# Connectors.net
KiCad netlist of a schematic drawn in Altium Designer
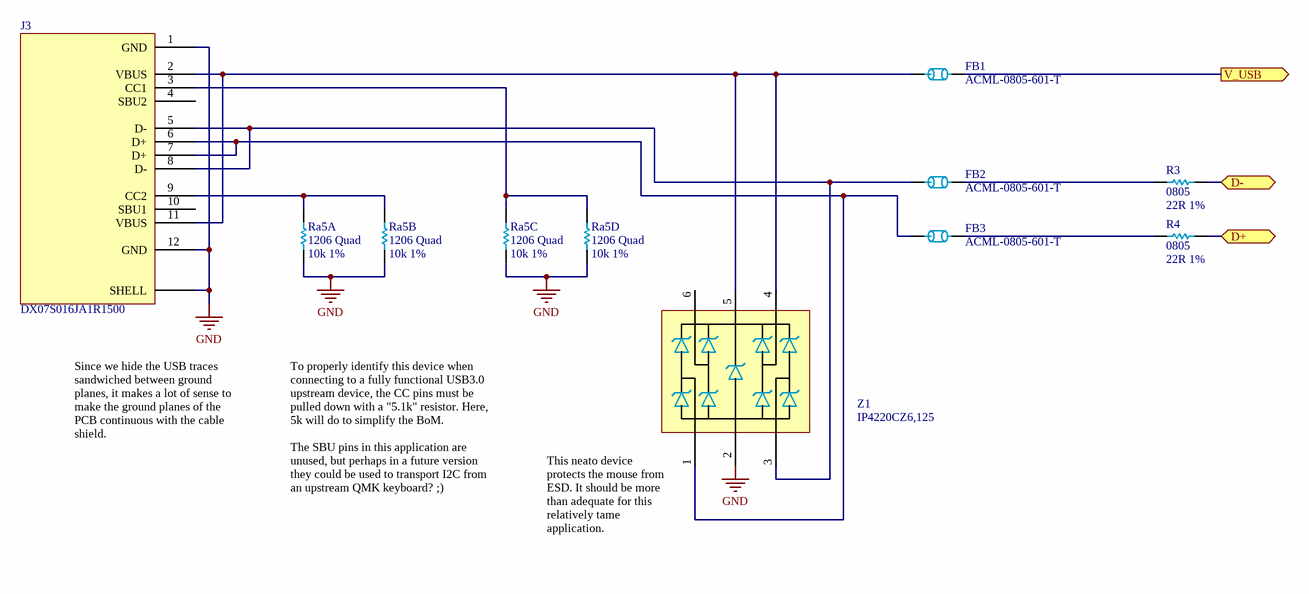
[diagram p0: Connectors.SchDoc]

(export (version "E")
  (design (tool "Eeschema 10.0.6"))
  (components
    (comp (ref "FB1")
      (value "ACML-0805-601-T")
      (footprint "0805")
      (description "FERRITE BEAD 600 OHM 0805 1LN")
      (libsource (lib "Chip_Passives") (part "ACML-0805-601-T"))
    )
    (comp (ref "FB2")
      (value "ACML-0805-601-T")
      (footprint "0805")
      (description "FERRITE BEAD 600 OHM 0805 1LN")
      (libsource (lib "Chip_Passives") (part "ACML-0805-601-T"))
    )
    (comp (ref "FB3")
      (value "ACML-0805-601-T")
      (footprint "0805")
      (description "FERRITE BEAD 600 OHM 0805 1LN")
      (libsource (lib "Chip_Passives") (part "ACML-0805-601-T"))
    )
    (comp (ref "J3")
      (value "DX07S016JA1R1500")
      (footprint "DX07S016JA1R1500")
      (libsource (lib "Connectors") (part "DX07S016JA1R1500"))
    )
    (comp (ref "R3")
      (value "0805")
      (footprint "0805")
      (description "Chip resistor")
      (fields (field (name "ALTIUM_VALUE") "22R 1%"))
      (libsource (lib "Chip_Passives") (part "Res 22R 1% 0805"))
    )
    (comp (ref "R4")
      (value "0805")
      (footprint "0805")
      (description "Chip resistor")
      (fields (field (name "ALTIUM_VALUE") "22R 1%"))
      (libsource (lib "Chip_Passives") (part "Res 22R 1% 0805"))
    )
    (comp (ref "Ra5")
      (value "1206 Quad")
      (footprint "4x 10k 1% - CAC-80P320X160-8M")
      (description "Chip resistor")
      (fields (field (name "ALTIUM_VALUE") "10k 1%"))
      (libsource (lib "Chip_Passives") (part "Quad Res 10k 1% 1206"))
    )
    (comp (ref "Z1")
      (value "IP4220CZ6,125")
      (footprint "PESD3V3S4UD - SOT95P275X110-6N")
      (description "TVS DIODE 5.5V 6TSOP (Low capacitance, USB)")
      (libsource (lib "Diodes") (part "IP4220CZ6,125"))
    )
  )
  (nets
    (net (code "1") (name "/D+") (class "Default")
      (node (ref "R4") (pin "2") (pinfunction "2_2") (pintype "passive"))
    )
    (net (code "2") (name "/D-") (class "Default")
      (node (ref "R3") (pin "2") (pinfunction "2_2") (pintype "passive"))
    )
    (net (code "3") (name "/V_USB") (class "Default")
      (node (ref "FB1") (pin "2") (pinfunction "2_2") (pintype "passive"))
    )
    (net (code "4") (name "GND") (class "Default")
      (node (ref "J3") (pin "1") (pinfunction "GND_1") (pintype "passive"))
      (node (ref "J3") (pin "12") (pinfunction "GND_12") (pintype "passive"))
      (node (ref "J3") (pin "SHELL") (pinfunction "SHELL_SHELL") (pintype "passive"))
      (node (ref "Ra5") (pin "1") (pinfunction "1_1") (pintype "passive"))
      (node (ref "Ra5") (pin "2") (pinfunction "2_2") (pintype "passive"))
      (node (ref "Ra5") (pin "3") (pinfunction "3_3") (pintype "passive"))
      (node (ref "Ra5") (pin "4") (pinfunction "4_4") (pintype "passive"))
      (node (ref "Z1") (pin "2") (pinfunction "2_2") (pintype "passive"))
    )
    (net (code "5") (name "Net-(FB1-Pad1)") (class "Default")
      (node (ref "FB1") (pin "1") (pinfunction "1_1") (pintype "passive"))
      (node (ref "J3") (pin "11") (pinfunction "VBUS_11") (pintype "passive"))
      (node (ref "J3") (pin "2") (pinfunction "VBUS_2") (pintype "passive"))
      (node (ref "Z1") (pin "4") (pinfunction "4_4") (pintype "passive"))
      (node (ref "Z1") (pin "5") (pinfunction "5_5") (pintype "passive"))
    )
    (net (code "6") (name "Net-(FB2-Pad1)") (class "Default")
      (node (ref "FB2") (pin "1") (pinfunction "1_1") (pintype "passive"))
      (node (ref "J3") (pin "5") (pinfunction "D-_5") (pintype "passive"))
      (node (ref "J3") (pin "8") (pinfunction "D-_8") (pintype "passive"))
      (node (ref "Z1") (pin "3") (pinfunction "3_3") (pintype "passive"))
    )
    (net (code "7") (name "Net-(FB2-Pad2)") (class "Default")
      (node (ref "FB2") (pin "2") (pinfunction "2_2") (pintype "passive"))
      (node (ref "R3") (pin "1") (pinfunction "1_1") (pintype "passive"))
    )
    (net (code "8") (name "Net-(FB3-Pad1)") (class "Default")
      (node (ref "FB3") (pin "1") (pinfunction "1_1") (pintype "passive"))
      (node (ref "J3") (pin "6") (pinfunction "D+_6") (pintype "passive"))
      (node (ref "J3") (pin "7") (pinfunction "D+_7") (pintype "passive"))
      (node (ref "Z1") (pin "1") (pinfunction "1_1") (pintype "passive"))
    )
    (net (code "9") (name "Net-(FB3-Pad2)") (class "Default")
      (node (ref "FB3") (pin "2") (pinfunction "2_2") (pintype "passive"))
      (node (ref "R4") (pin "1") (pinfunction "1_1") (pintype "passive"))
    )
    (net (code "10") (name "Net-(J3-CC1)") (class "Default")
      (node (ref "J3") (pin "3") (pinfunction "CC1_3") (pintype "passive"))
      (node (ref "Ra5") (pin "5") (pinfunction "5_5") (pintype "passive"))
      (node (ref "Ra5") (pin "6") (pinfunction "6_6") (pintype "passive"))
    )
    (net (code "11") (name "Net-(J3-CC2)") (class "Default")
      (node (ref "J3") (pin "9") (pinfunction "CC2_9") (pintype "passive"))
      (node (ref "Ra5") (pin "7") (pinfunction "7_7") (pintype "passive"))
      (node (ref "Ra5") (pin "8") (pinfunction "8_8") (pintype "passive"))
    )
    (net (code "12") (name "unconnected-(J3-SBU1-Pad10)") (class "Default")
      (node (ref "J3") (pin "10") (pinfunction "SBU1_10") (pintype "passive"))
    )
    (net (code "13") (name "unconnected-(J3-SBU2-Pad4)") (class "Default")
      (node (ref "J3") (pin "4") (pinfunction "SBU2_4") (pintype "passive"))
    )
    (net (code "14") (name "unconnected-(Z1-Pad6)") (class "Default")
      (node (ref "Z1") (pin "6") (pinfunction "6_6") (pintype "passive"))
    )
  )
)
